# SCH_anne_sch2_2023-06-27.net
KiCad netlist of a schematic drawn in EasyEDA
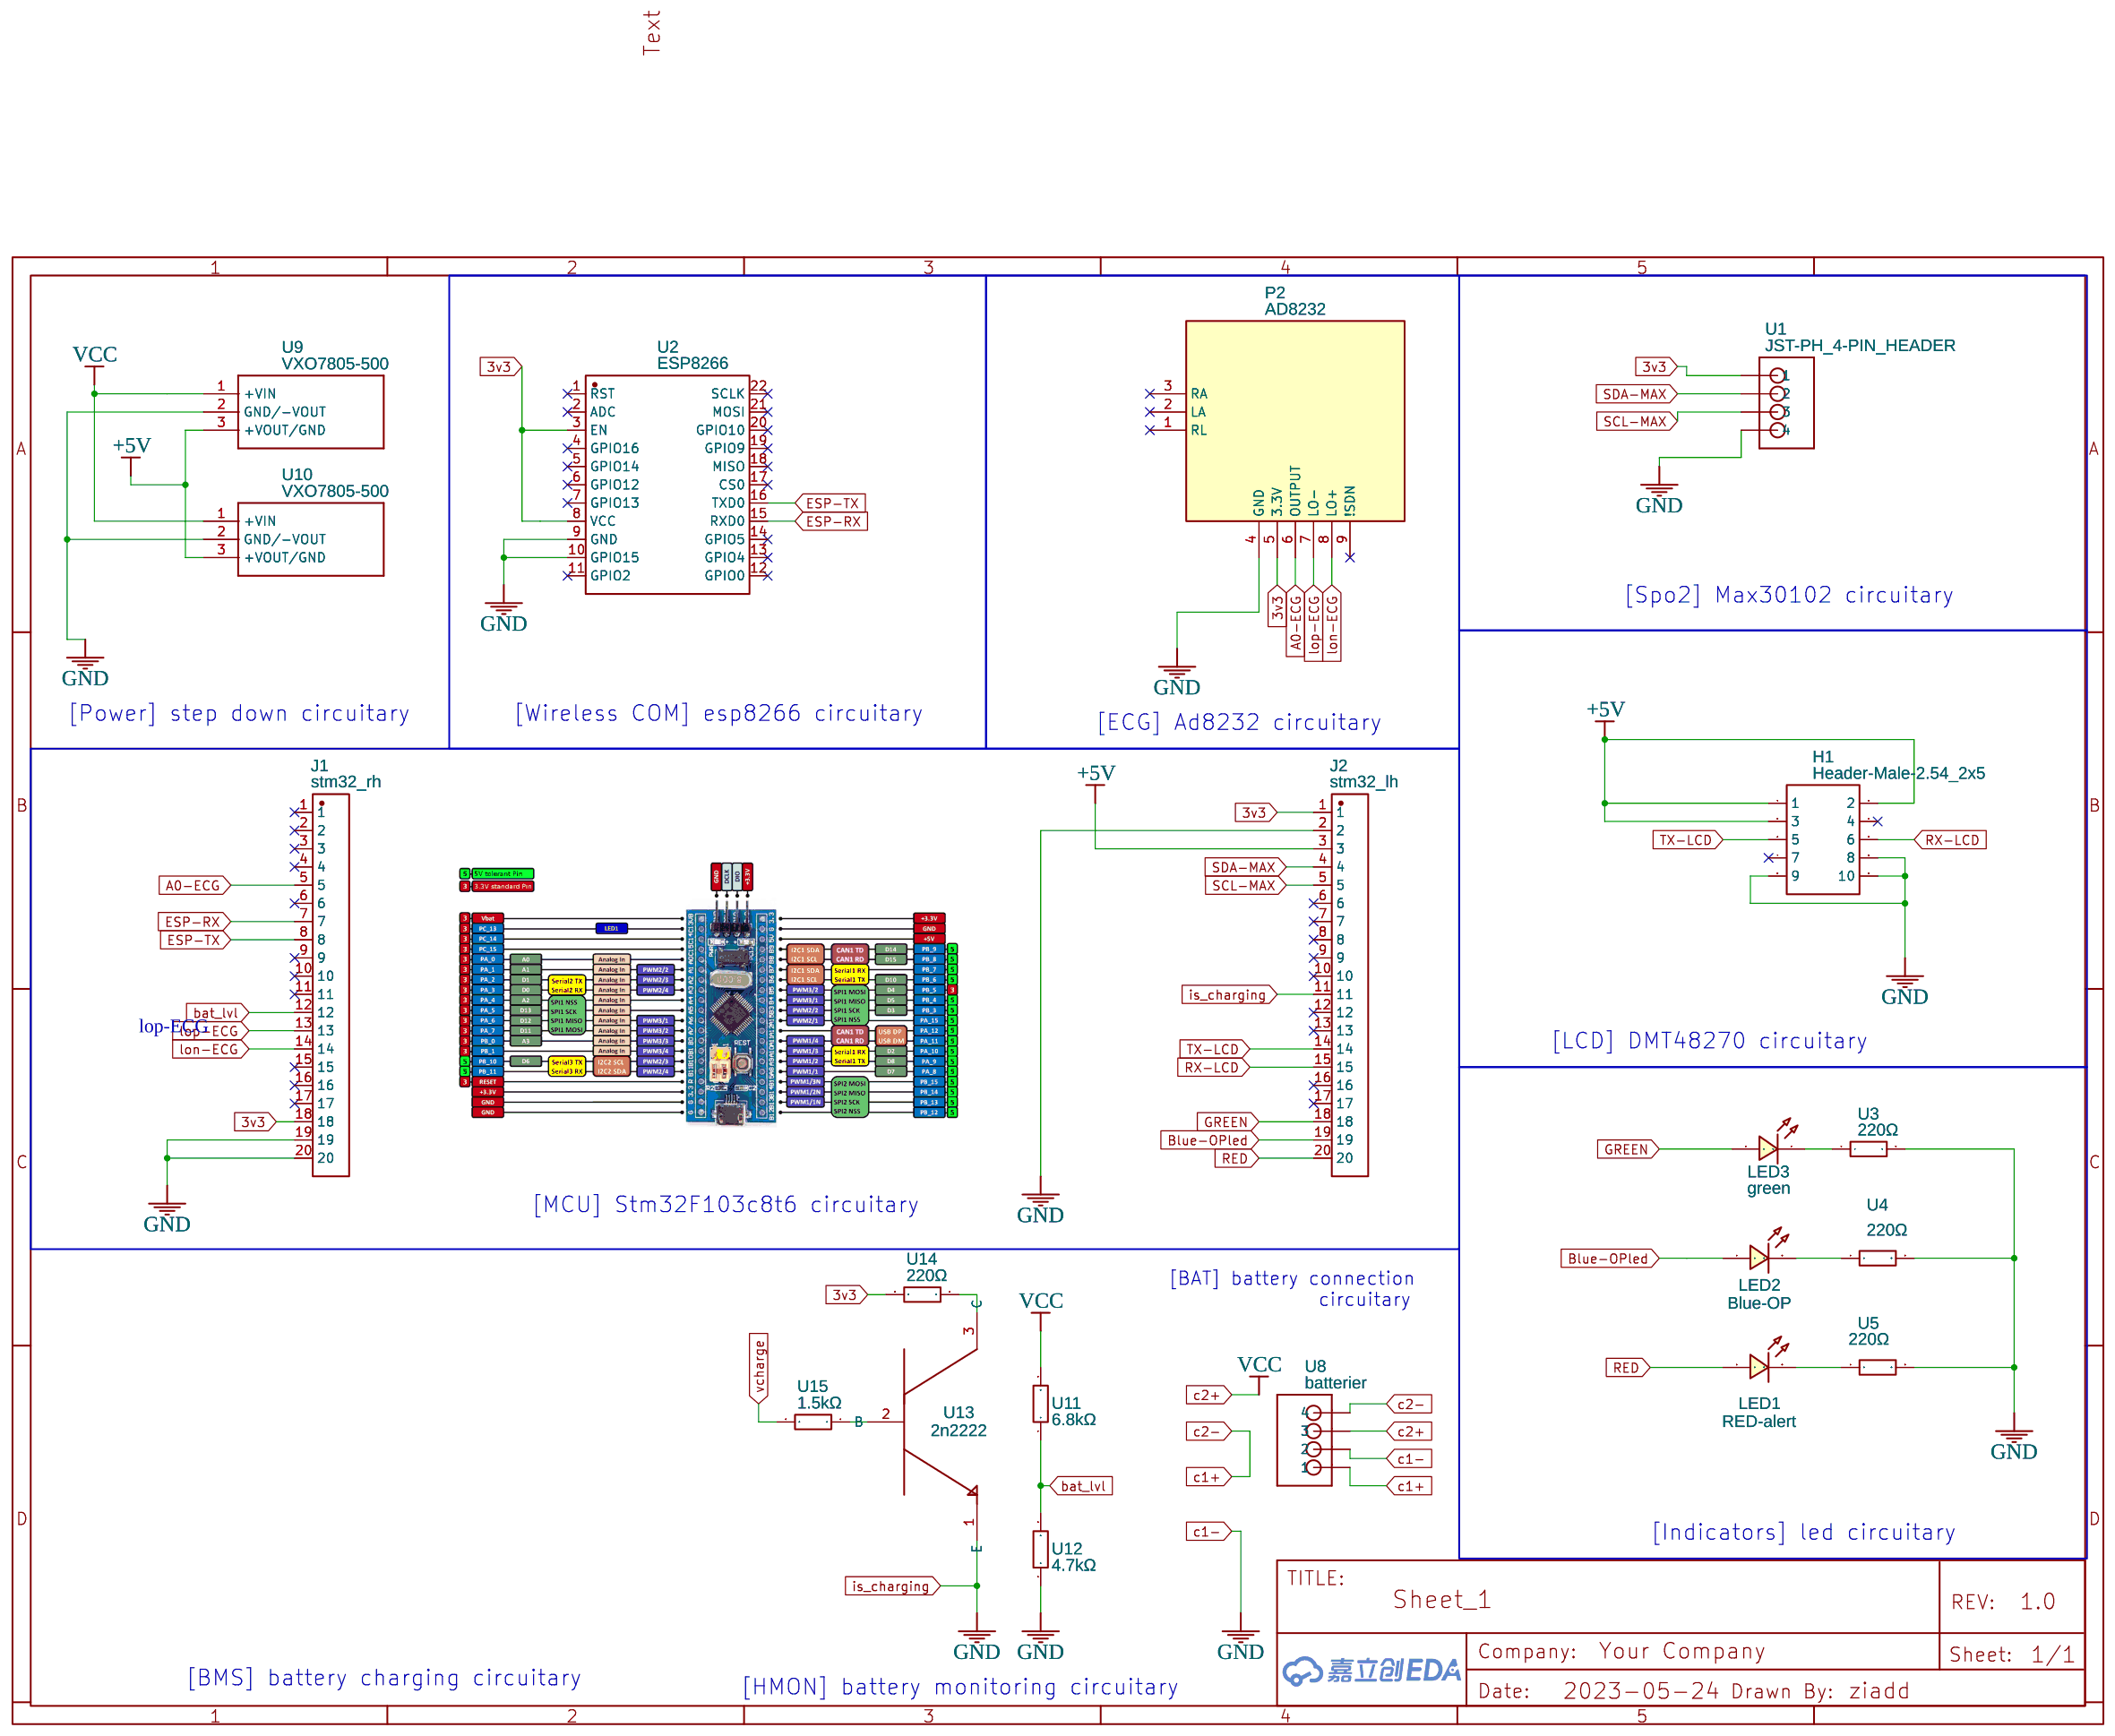
[diagram p0: schematic sheet]

(export (version "E")
  (design (tool "Eeschema 10.0.6"))
  (components
    (comp (ref "H1")
      (value "Header-Male-2.54_2x5")
      (fields
        (field (name "BOM_Manufacturer Part") "2*5pHeaders  Pins 2.54mm")
        (field (name "BOM_Supplier Part") "C28207")
      )
      (libsource (lib "") (part "Header-Male-2.54_2x5"))
    )
    (comp (ref "J1")
      (value "stm32_rh")
      (fields
        (field (name "BOM_Manufacturer Part") "2.54-1*20P直针")
        (field (name "BOM_Supplier Part") "C50981")
      )
      (libsource (lib "") (part "Header-Male-2.54_1x20"))
    )
    (comp (ref "J2")
      (value "stm32_lh")
      (fields
        (field (name "BOM_Manufacturer Part") "2.54-1*20P直针")
        (field (name "BOM_Supplier Part") "C50981")
      )
      (libsource (lib "") (part "Header-Male-2.54_1x20"))
    )
    (comp (ref "LED1")
      (value "RED-alert")
      (fields
        (field (name "BOM_Manufacturer Part") "19-217/R6C-AL1M2VY/3T")
        (field (name "BOM_Supplier Part") "C72044")
      )
      (libsource (lib "") (part "LED-0603_R"))
    )
    (comp (ref "LED2")
      (value "Blue-OP")
      (fields
        (field (name "BOM_Manufacturer Part") "19-217/R6C-AL1M2VY/3T")
        (field (name "BOM_Supplier Part") "C72044")
      )
      (libsource (lib "") (part "LED-0603_R"))
    )
    (comp (ref "LED3")
      (value "green")
      (fields
        (field (name "BOM_Manufacturer Part") "19-217/R6C-AL1M2VY/3T")
        (field (name "BOM_Supplier Part") "C72044")
      )
      (libsource (lib "") (part "LED-0603_R"))
    )
    (comp (ref "P2")
      (value "AD8232")
      (fields (field (name "BOM_Supplier Part") "12587"))
      (libsource (lib "") (part "AD8232"))
    )
    (comp (ref "U1") (value "JST-PH_4-PIN_HEADER") (libsource (lib "") (part "JST-PH_4-PIN_HEADER_1")))
    (comp (ref "U2")
      (value "ESP8266")
      (fields (field (name "BOM_Supplier Part") "C9900003049"))
      (libsource (lib "") (part "ESP8266"))
    )
    (comp (ref "U3")
      (value "220Ω")
      (fields
        (field (name "BOM_Manufacturer Part") "CR1/4W-2K7±5%-ST26")
        (field (name "BOM_Supplier Part") "C2894624")
      )
      (libsource (lib "") (part "CR1/4W-2K7±5%-ST26_2"))
    )
    (comp (ref "U4")
      (value "220Ω")
      (fields
        (field (name "BOM_Manufacturer Part") "CR1/4W-2K7±5%-ST26")
        (field (name "BOM_Supplier Part") "C2894624")
      )
      (libsource (lib "") (part "CR1/4W-2K7±5%-ST26_2"))
    )
    (comp (ref "U5")
      (value "220Ω")
      (fields
        (field (name "BOM_Manufacturer Part") "CR1/4W-2K7±5%-ST26")
        (field (name "BOM_Supplier Part") "C2894624")
      )
      (libsource (lib "") (part "CR1/4W-2K7±5%-ST26_2"))
    )
    (comp (ref "U8") (value "batterier") (libsource (lib "") (part "JST-PH_4-PIN_HEADER")))
    (comp (ref "U9") (value "VXO7805-500") (libsource (lib "") (part "VXO7805-500")))
    (comp (ref "U10") (value "VXO7805-500") (libsource (lib "") (part "VXO7805-500")))
    (comp (ref "U11")
      (value "6.8kΩ")
      (fields
        (field (name "BOM_Manufacturer Part") "CR1/4W-2K7±5%-ST26")
        (field (name "BOM_Supplier Part") "C2894624")
      )
      (libsource (lib "") (part "CR1/4W-2K7±5%-ST26"))
    )
    (comp (ref "U12")
      (value "4.7kΩ")
      (fields
        (field (name "BOM_Manufacturer Part") "CR1/4W-2K7±5%-ST26")
        (field (name "BOM_Supplier Part") "C2894624")
      )
      (libsource (lib "") (part "CR1/4W-2K7±5%-ST26"))
    )
    (comp (ref "U13") (value "2n2222") (libsource (lib "") (part "2n2222")))
    (comp (ref "U14")
      (value "220Ω")
      (fields
        (field (name "BOM_Manufacturer Part") "CR1/4W-2K7±5%-ST26")
        (field (name "BOM_Supplier Part") "C2894624")
      )
      (libsource (lib "") (part "CR1/4W-2K7±5%-ST26_1"))
    )
    (comp (ref "U15")
      (value "1.5kΩ")
      (fields
        (field (name "BOM_Manufacturer Part") "CR1/4W-2K7±5%-ST26")
        (field (name "BOM_Supplier Part") "C2894624")
      )
      (libsource (lib "") (part "CR1/4W-2K7±5%-ST26_1"))
    )
  )
  (nets
    (net (code "1") (name "+5V") (class "Default")
      (node (ref "H1") (pin "1") (pinfunction "1_1") (pintype "input"))
      (node (ref "H1") (pin "2") (pinfunction "2_2") (pintype "input"))
      (node (ref "H1") (pin "3") (pinfunction "3_3") (pintype "input"))
      (node (ref "J2") (pin "3") (pinfunction "3_3") (pintype "unspecified"))
      (node (ref "U10") (pin "3") (pinfunction "+VOUT/GND_3") (pintype "bidirectional"))
      (node (ref "U9") (pin "3") (pinfunction "+VOUT/GND_3") (pintype "bidirectional"))
    )
    (net (code "2") (name "3v3") (class "Default")
      (node (ref "J1") (pin "18") (pinfunction "18_18") (pintype "unspecified"))
      (node (ref "J2") (pin "1") (pinfunction "1_1") (pintype "unspecified"))
      (node (ref "P2") (pin "5") (pinfunction "3.3V_5") (pintype "unspecified"))
      (node (ref "U1") (pin "P1") (pinfunction "1_P1") (pintype "unspecified"))
      (node (ref "U14") (pin "2") (pinfunction "2_2") (pintype "unspecified"))
      (node (ref "U2") (pin "3") (pinfunction "EN_3") (pintype "unspecified"))
      (node (ref "U2") (pin "8") (pinfunction "VCC_8") (pintype "unspecified"))
    )
    (net (code "3") (name "A0-ECG") (class "Default")
      (node (ref "J1") (pin "5") (pinfunction "5_5") (pintype "unspecified"))
      (node (ref "P2") (pin "6") (pinfunction "OUTPUT_6") (pintype "unspecified"))
    )
    (net (code "4") (name "Blue-OPled") (class "Default")
      (node (ref "J2") (pin "19") (pinfunction "19_19") (pintype "unspecified"))
      (node (ref "LED2") (pin "1") (pinfunction "1_1") (pintype "unspecified"))
    )
    (net (code "5") (name "ESP-RX") (class "Default")
      (node (ref "J1") (pin "7") (pinfunction "7_7") (pintype "unspecified"))
      (node (ref "U2") (pin "15") (pinfunction "RXD0_15") (pintype "unspecified"))
    )
    (net (code "6") (name "ESP-TX") (class "Default")
      (node (ref "J1") (pin "8") (pinfunction "8_8") (pintype "unspecified"))
      (node (ref "U2") (pin "16") (pinfunction "TXD0_16") (pintype "unspecified"))
    )
    (net (code "7") (name "GREEN") (class "Default")
      (node (ref "J2") (pin "18") (pinfunction "18_18") (pintype "unspecified"))
      (node (ref "LED3") (pin "1") (pinfunction "1_1") (pintype "unspecified"))
    )
    (net (code "8") (name "Net-(LED1-Pad2)") (class "Default")
      (node (ref "LED1") (pin "2") (pinfunction "2_2") (pintype "unspecified"))
      (node (ref "U5") (pin "1") (pinfunction "1_1") (pintype "unspecified"))
    )
    (net (code "9") (name "Net-(LED2-Pad2)") (class "Default")
      (node (ref "LED2") (pin "2") (pinfunction "2_2") (pintype "unspecified"))
      (node (ref "U4") (pin "1") (pinfunction "1_1") (pintype "unspecified"))
    )
    (net (code "10") (name "Net-(LED3-Pad2)") (class "Default")
      (node (ref "LED3") (pin "2") (pinfunction "2_2") (pintype "unspecified"))
      (node (ref "U3") (pin "1") (pinfunction "1_1") (pintype "unspecified"))
    )
    (net (code "11") (name "RED") (class "Default")
      (node (ref "J2") (pin "20") (pinfunction "20_20") (pintype "unspecified"))
      (node (ref "LED1") (pin "1") (pinfunction "1_1") (pintype "unspecified"))
    )
    (net (code "12") (name "RX-LCD") (class "Default")
      (node (ref "H1") (pin "6") (pinfunction "6_6") (pintype "input"))
      (node (ref "J2") (pin "15") (pinfunction "15_15") (pintype "unspecified"))
    )
    (net (code "13") (name "SCL-MAX") (class "Default")
      (node (ref "J2") (pin "5") (pinfunction "5_5") (pintype "unspecified"))
      (node (ref "U1") (pin "P3") (pinfunction "3_P3") (pintype "unspecified"))
    )
    (net (code "14") (name "SDA-MAX") (class "Default")
      (node (ref "J2") (pin "4") (pinfunction "4_4") (pintype "unspecified"))
      (node (ref "U1") (pin "P2") (pinfunction "2_P2") (pintype "unspecified"))
    )
    (net (code "15") (name "TX-LCD") (class "Default")
      (node (ref "H1") (pin "5") (pinfunction "5_5") (pintype "input"))
      (node (ref "J2") (pin "14") (pinfunction "14_14") (pintype "unspecified"))
    )
    (net (code "16") (name "bat_lvl") (class "Default")
      (node (ref "J1") (pin "12") (pinfunction "12_12") (pintype "unspecified"))
      (node (ref "U11") (pin "1") (pinfunction "1_1") (pintype "unspecified"))
      (node (ref "U12") (pin "2") (pinfunction "2_2") (pintype "unspecified"))
    )
    (net (code "17") (name "c1+") (class "Default")
      (node (ref "U8") (pin "P1") (pinfunction "1_P1") (pintype "unspecified"))
      (node (ref "U8") (pin "P4") (pinfunction "4_P4") (pintype "unspecified"))
    )
    (net (code "18") (name "c1-") (class "Default")
      (node (ref "H1") (pin "10") (pinfunction "10_10") (pintype "input"))
      (node (ref "H1") (pin "8") (pinfunction "8_8") (pintype "input"))
      (node (ref "H1") (pin "9") (pinfunction "9_9") (pintype "input"))
      (node (ref "J1") (pin "19") (pinfunction "19_19") (pintype "unspecified"))
      (node (ref "J1") (pin "20") (pinfunction "20_20") (pintype "unspecified"))
      (node (ref "J2") (pin "11") (pinfunction "11_11") (pintype "unspecified"))
      (node (ref "J2") (pin "2") (pinfunction "2_2") (pintype "unspecified"))
      (node (ref "P2") (pin "4") (pinfunction "GND_4") (pintype "unspecified"))
      (node (ref "U1") (pin "P4") (pinfunction "4_P4") (pintype "unspecified"))
      (node (ref "U10") (pin "2") (pinfunction "GND/-VOUT_2") (pintype "bidirectional"))
      (node (ref "U12") (pin "1") (pinfunction "1_1") (pintype "unspecified"))
      (node (ref "U2") (pin "10") (pinfunction "GPIO15_10") (pintype "unspecified"))
      (node (ref "U2") (pin "9") (pinfunction "GND_9") (pintype "unspecified"))
      (node (ref "U3") (pin "2") (pinfunction "2_2") (pintype "unspecified"))
      (node (ref "U4") (pin "2") (pinfunction "2_2") (pintype "unspecified"))
      (node (ref "U5") (pin "2") (pinfunction "2_2") (pintype "unspecified"))
      (node (ref "U8") (pin "P2") (pinfunction "2_P2") (pintype "unspecified"))
      (node (ref "U9") (pin "2") (pinfunction "GND/-VOUT_2") (pintype "bidirectional"))
    )
    (net (code "19") (name "c2+") (class "Default")
      (node (ref "U10") (pin "1") (pinfunction "+VIN_1") (pintype "bidirectional"))
      (node (ref "U11") (pin "2") (pinfunction "2_2") (pintype "unspecified"))
      (node (ref "U8") (pin "P3") (pinfunction "3_P3") (pintype "unspecified"))
      (node (ref "U9") (pin "1") (pinfunction "+VIN_1") (pintype "bidirectional"))
    )
    (net (code "20") (name "lon-ECG") (class "Default")
      (node (ref "J1") (pin "14") (pinfunction "14_14") (pintype "unspecified"))
      (node (ref "P2") (pin "8") (pinfunction "LO+_8") (pintype "unspecified"))
    )
    (net (code "21") (name "lop-ECG") (class "Default")
      (node (ref "J1") (pin "13") (pinfunction "13_13") (pintype "unspecified"))
      (node (ref "P2") (pin "7") (pinfunction "LO-_7") (pintype "unspecified"))
    )
    (net (code "22") (name "unconnected-(H1-Pad4)") (class "Default")
      (node (ref "H1") (pin "4") (pinfunction "4_4") (pintype "input+no_connect"))
    )
    (net (code "23") (name "unconnected-(H1-Pad7)") (class "Default")
      (node (ref "H1") (pin "7") (pinfunction "7_7") (pintype "input+no_connect"))
    )
    (net (code "24") (name "unconnected-(J1-Pad1)") (class "Default")
      (node (ref "J1") (pin "1") (pinfunction "1_1") (pintype "unspecified+no_connect"))
    )
    (net (code "25") (name "unconnected-(J1-Pad2)") (class "Default")
      (node (ref "J1") (pin "2") (pinfunction "2_2") (pintype "unspecified+no_connect"))
    )
    (net (code "26") (name "unconnected-(J1-Pad3)") (class "Default")
      (node (ref "J1") (pin "3") (pinfunction "3_3") (pintype "unspecified+no_connect"))
    )
    (net (code "27") (name "unconnected-(J1-Pad4)") (class "Default")
      (node (ref "J1") (pin "4") (pinfunction "4_4") (pintype "unspecified+no_connect"))
    )
    (net (code "28") (name "unconnected-(J1-Pad6)") (class "Default")
      (node (ref "J1") (pin "6") (pinfunction "6_6") (pintype "unspecified+no_connect"))
    )
    (net (code "29") (name "unconnected-(J1-Pad9)") (class "Default")
      (node (ref "J1") (pin "9") (pinfunction "9_9") (pintype "unspecified+no_connect"))
    )
    (net (code "30") (name "unconnected-(J1-Pad10)") (class "Default")
      (node (ref "J1") (pin "10") (pinfunction "10_10") (pintype "unspecified+no_connect"))
    )
    (net (code "31") (name "unconnected-(J1-Pad11)") (class "Default")
      (node (ref "J1") (pin "11") (pinfunction "11_11") (pintype "unspecified+no_connect"))
    )
    (net (code "32") (name "unconnected-(J1-Pad15)") (class "Default")
      (node (ref "J1") (pin "15") (pinfunction "15_15") (pintype "unspecified+no_connect"))
    )
    (net (code "33") (name "unconnected-(J1-Pad16)") (class "Default")
      (node (ref "J1") (pin "16") (pinfunction "16_16") (pintype "unspecified+no_connect"))
    )
    (net (code "34") (name "unconnected-(J1-Pad17)") (class "Default")
      (node (ref "J1") (pin "17") (pinfunction "17_17") (pintype "unspecified+no_connect"))
    )
    (net (code "35") (name "unconnected-(J2-Pad6)") (class "Default")
      (node (ref "J2") (pin "6") (pinfunction "6_6") (pintype "unspecified+no_connect"))
    )
    (net (code "36") (name "unconnected-(J2-Pad7)") (class "Default")
      (node (ref "J2") (pin "7") (pinfunction "7_7") (pintype "unspecified+no_connect"))
    )
    (net (code "37") (name "unconnected-(J2-Pad8)") (class "Default")
      (node (ref "J2") (pin "8") (pinfunction "8_8") (pintype "unspecified+no_connect"))
    )
    (net (code "38") (name "unconnected-(J2-Pad9)") (class "Default")
      (node (ref "J2") (pin "9") (pinfunction "9_9") (pintype "unspecified+no_connect"))
    )
    (net (code "39") (name "unconnected-(J2-Pad10)") (class "Default")
      (node (ref "J2") (pin "10") (pinfunction "10_10") (pintype "unspecified+no_connect"))
    )
    (net (code "40") (name "unconnected-(J2-Pad12)") (class "Default")
      (node (ref "J2") (pin "12") (pinfunction "12_12") (pintype "unspecified+no_connect"))
    )
    (net (code "41") (name "unconnected-(J2-Pad13)") (class "Default")
      (node (ref "J2") (pin "13") (pinfunction "13_13") (pintype "unspecified+no_connect"))
    )
    (net (code "42") (name "unconnected-(J2-Pad16)") (class "Default")
      (node (ref "J2") (pin "16") (pinfunction "16_16") (pintype "unspecified+no_connect"))
    )
    (net (code "43") (name "unconnected-(J2-Pad17)") (class "Default")
      (node (ref "J2") (pin "17") (pinfunction "17_17") (pintype "unspecified+no_connect"))
    )
    (net (code "44") (name "unconnected-(P2-!SDN-Pad9)") (class "Default")
      (node (ref "P2") (pin "9") (pinfunction "!SDN_9") (pintype "unspecified+no_connect"))
    )
    (net (code "45") (name "unconnected-(P2-LA-Pad2)") (class "Default")
      (node (ref "P2") (pin "2") (pinfunction "LA_2") (pintype "unspecified+no_connect"))
    )
    (net (code "46") (name "unconnected-(P2-RA-Pad3)") (class "Default")
      (node (ref "P2") (pin "3") (pinfunction "RA_3") (pintype "unspecified+no_connect"))
    )
    (net (code "47") (name "unconnected-(P2-RL-Pad1)") (class "Default")
      (node (ref "P2") (pin "1") (pinfunction "RL_1") (pintype "unspecified+no_connect"))
    )
    (net (code "48") (name "unconnected-(U2-ADC-Pad2)") (class "Default")
      (node (ref "U2") (pin "2") (pinfunction "ADC_2") (pintype "unspecified+no_connect"))
    )
    (net (code "49") (name "unconnected-(U2-CS0-Pad17)") (class "Default")
      (node (ref "U2") (pin "17") (pinfunction "CS0_17") (pintype "unspecified+no_connect"))
    )
    (net (code "50") (name "unconnected-(U2-GPIO0-Pad12)") (class "Default")
      (node (ref "U2") (pin "12") (pinfunction "GPIO0_12") (pintype "unspecified+no_connect"))
    )
    (net (code "51") (name "unconnected-(U2-GPIO2-Pad11)") (class "Default")
      (node (ref "U2") (pin "11") (pinfunction "GPIO2_11") (pintype "unspecified+no_connect"))
    )
    (net (code "52") (name "unconnected-(U2-GPIO4-Pad13)") (class "Default")
      (node (ref "U2") (pin "13") (pinfunction "GPIO4_13") (pintype "unspecified+no_connect"))
    )
    (net (code "53") (name "unconnected-(U2-GPIO5-Pad14)") (class "Default")
      (node (ref "U2") (pin "14") (pinfunction "GPIO5_14") (pintype "unspecified+no_connect"))
    )
    (net (code "54") (name "unconnected-(U2-GPIO9-Pad19)") (class "Default")
      (node (ref "U2") (pin "19") (pinfunction "GPIO9_19") (pintype "unspecified+no_connect"))
    )
    (net (code "55") (name "unconnected-(U2-GPIO10-Pad20)") (class "Default")
      (node (ref "U2") (pin "20") (pinfunction "GPIO10_20") (pintype "unspecified+no_connect"))
    )
    (net (code "56") (name "unconnected-(U2-GPIO12-Pad6)") (class "Default")
      (node (ref "U2") (pin "6") (pinfunction "GPIO12_6") (pintype "unspecified+no_connect"))
    )
    (net (code "57") (name "unconnected-(U2-GPIO13-Pad7)") (class "Default")
      (node (ref "U2") (pin "7") (pinfunction "GPIO13_7") (pintype "unspecified+no_connect"))
    )
    (net (code "58") (name "unconnected-(U2-GPIO14-Pad5)") (class "Default")
      (node (ref "U2") (pin "5") (pinfunction "GPIO14_5") (pintype "unspecified+no_connect"))
    )
    (net (code "59") (name "unconnected-(U2-GPIO16-Pad4)") (class "Default")
      (node (ref "U2") (pin "4") (pinfunction "GPIO16_4") (pintype "unspecified+no_connect"))
    )
    (net (code "60") (name "unconnected-(U2-MISO-Pad18)") (class "Default")
      (node (ref "U2") (pin "18") (pinfunction "MISO_18") (pintype "unspecified+no_connect"))
    )
    (net (code "61") (name "unconnected-(U2-MOSI-Pad21)") (class "Default")
      (node (ref "U2") (pin "21") (pinfunction "MOSI_21") (pintype "unspecified+no_connect"))
    )
    (net (code "62") (name "unconnected-(U2-RST-Pad1)") (class "Default")
      (node (ref "U2") (pin "1") (pinfunction "RST_1") (pintype "unspecified+no_connect"))
    )
    (net (code "63") (name "unconnected-(U2-SCLK-Pad22)") (class "Default")
      (node (ref "U2") (pin "22") (pinfunction "SCLK_22") (pintype "unspecified+no_connect"))
    )
    (net (code "64") (name "unconnected-(U13-B-Pad2)") (class "Default")
      (node (ref "U13") (pin "2") (pinfunction "B_2") (pintype "unspecified"))
    )
    (net (code "65") (name "unconnected-(U13-C-Pad3)") (class "Default")
      (node (ref "U13") (pin "3") (pinfunction "C_3") (pintype "unspecified"))
    )
    (net (code "66") (name "unconnected-(U13-E-Pad1)") (class "Default")
      (node (ref "U13") (pin "1") (pinfunction "E_1") (pintype "unspecified"))
    )
    (net (code "67") (name "unconnected-(U14-Pad1)") (class "Default")
      (node (ref "U14") (pin "1") (pinfunction "1_1") (pintype "unspecified"))
    )
    (net (code "68") (name "unconnected-(U15-Pad1)") (class "Default")
      (node (ref "U15") (pin "1") (pinfunction "1_1") (pintype "unspecified"))
    )
    (net (code "69") (name "vcharge") (class "Default")
      (node (ref "U15") (pin "2") (pinfunction "2_2") (pintype "unspecified"))
    )
  )
)
